# mosfet_example.net
KiCad netlist of a schematic drawn in EAGLE
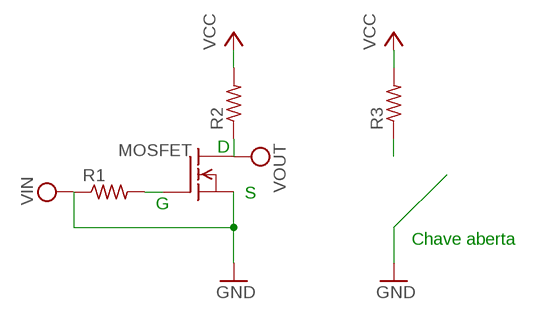
[diagram p0: schematic, sheet 1]

(export (version "E")
  (design (tool "Eeschema 10.0.6"))
  (components
    (comp (ref "MOSFET")
      (value "BSS97")
      (footprint "eagle-import:TO202")
      (libsource (lib "eagle-import") (part "BSS97"))
    )
    (comp (ref "R1")
      (value "R-US_0204/2V")
      (footprint "eagle-import:0204V")
      (libsource (lib "eagle-import") (part "R-US_0204/2V"))
    )
    (comp (ref "R2")
      (value "R-US_0204/2V")
      (footprint "eagle-import:0204V")
      (libsource (lib "eagle-import") (part "R-US_0204/2V"))
    )
    (comp (ref "R3")
      (value "R-US_0204/2V")
      (footprint "eagle-import:0204V")
      (libsource (lib "eagle-import") (part "R-US_0204/2V"))
    )
  )
  (nets
    (net (code "1") (name "GND") (class "Default")
      (node (ref "MOSFET") (pin "1") (pinfunction "S_1") (pintype "passive"))
      (node (ref "R1") (pin "1") (pinfunction "1_1") (pintype "passive"))
    )
    (net (code "2") (name "Net-(MOSFET-D)") (class "Default")
      (node (ref "MOSFET") (pin "2") (pinfunction "D_2") (pintype "passive"))
      (node (ref "R2") (pin "1") (pinfunction "1_1") (pintype "passive"))
    )
    (net (code "3") (name "Net-(MOSFET-G)") (class "Default")
      (node (ref "MOSFET") (pin "3") (pinfunction "G_3") (pintype "passive"))
      (node (ref "R1") (pin "2") (pinfunction "2_2") (pintype "passive"))
    )
    (net (code "4") (name "VCC") (class "Default")
      (node (ref "R2") (pin "2") (pinfunction "2_2") (pintype "passive"))
      (node (ref "R3") (pin "2") (pinfunction "2_2") (pintype "passive"))
    )
    (net (code "7") (name "unconnected-(R3-Pad1)") (class "Default")
      (node (ref "R3") (pin "1") (pinfunction "1_1") (pintype "passive"))
    )
  )
)
